# Power-Resistor-Breakout-5W-v001.net
KiCad netlist of a schematic drawn in EAGLE
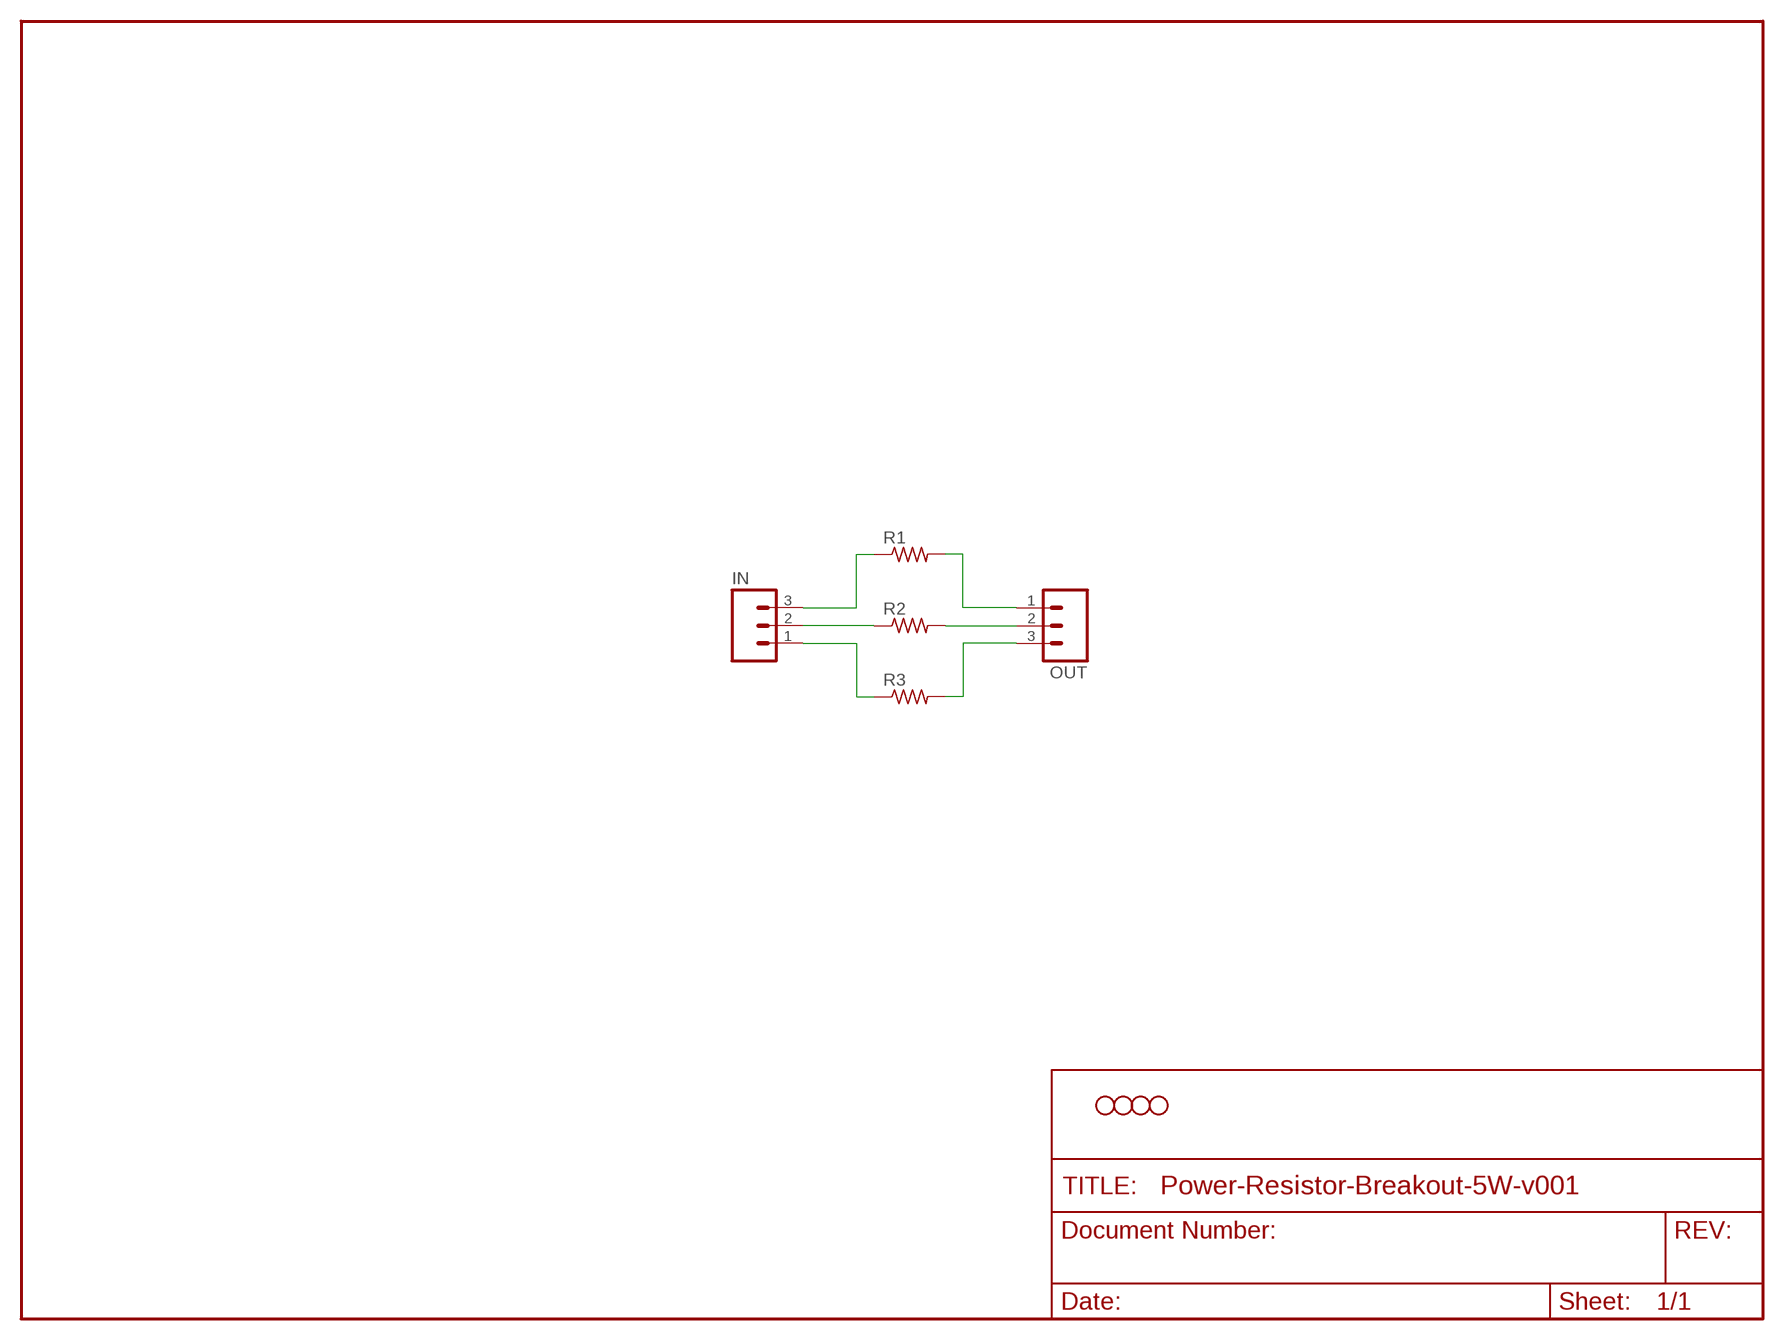
[diagram p0: schematic, sheet 1]

(export (version "E")
  (design (tool "Eeschema 10.0.6"))
  (components
    (comp (ref "IN")
      (value "M03PTH")
      (footprint "eagle-import:1X03")
      (libsource (lib "eagle-import") (part "M03PTH"))
    )
    (comp (ref "JP1")
      (value "STAND-OFF")
      (footprint "eagle-import:STAND-OFF")
      (libsource (lib "eagle-import") (part "STAND-OFF"))
    )
    (comp (ref "JP2")
      (value "STAND-OFF")
      (footprint "eagle-import:STAND-OFF")
      (libsource (lib "eagle-import") (part "STAND-OFF"))
    )
    (comp (ref "JP3")
      (value "STAND-OFF")
      (footprint "eagle-import:STAND-OFF")
      (libsource (lib "eagle-import") (part "STAND-OFF"))
    )
    (comp (ref "JP4")
      (value "STAND-OFF")
      (footprint "eagle-import:STAND-OFF")
      (libsource (lib "eagle-import") (part "STAND-OFF"))
    )
    (comp (ref "OUT")
      (value "M03PTH")
      (footprint "eagle-import:1X03")
      (libsource (lib "eagle-import") (part "M03PTH"))
    )
    (comp (ref "R1")
      (value "R-US_0922/22")
      (footprint "eagle-import:0922_22")
      (libsource (lib "eagle-import") (part "R-US_0922/22"))
    )
    (comp (ref "R2")
      (value "R-US_0922/22")
      (footprint "eagle-import:0922_22")
      (libsource (lib "eagle-import") (part "R-US_0922/22"))
    )
    (comp (ref "R3")
      (value "R-US_0922/22")
      (footprint "eagle-import:0922_22")
      (libsource (lib "eagle-import") (part "R-US_0922/22"))
    )
  )
  (nets
    (net (code "1") (name "Net-(IN-Pad1)") (class "Default")
      (node (ref "IN") (pin "1") (pinfunction "1_1") (pintype "passive"))
      (node (ref "R3") (pin "1") (pinfunction "1_1") (pintype "passive"))
    )
    (net (code "2") (name "Net-(IN-Pad2)") (class "Default")
      (node (ref "IN") (pin "2") (pinfunction "2_2") (pintype "passive"))
      (node (ref "R2") (pin "1") (pinfunction "1_1") (pintype "passive"))
    )
    (net (code "3") (name "Net-(IN-Pad3)") (class "Default")
      (node (ref "IN") (pin "3") (pinfunction "3_3") (pintype "passive"))
      (node (ref "R1") (pin "1") (pinfunction "1_1") (pintype "passive"))
    )
    (net (code "4") (name "Net-(OUT-Pad1)") (class "Default")
      (node (ref "OUT") (pin "1") (pinfunction "1_1") (pintype "passive"))
      (node (ref "R1") (pin "2") (pinfunction "2_2") (pintype "passive"))
    )
    (net (code "5") (name "Net-(OUT-Pad2)") (class "Default")
      (node (ref "OUT") (pin "2") (pinfunction "2_2") (pintype "passive"))
      (node (ref "R2") (pin "2") (pinfunction "2_2") (pintype "passive"))
    )
    (net (code "6") (name "Net-(OUT-Pad3)") (class "Default")
      (node (ref "OUT") (pin "3") (pinfunction "3_3") (pintype "passive"))
      (node (ref "R3") (pin "2") (pinfunction "2_2") (pintype "passive"))
    )
  )
)
